# Ethernet_-_LAN8720A.net
KiCad netlist of a schematic drawn in Altium Designer
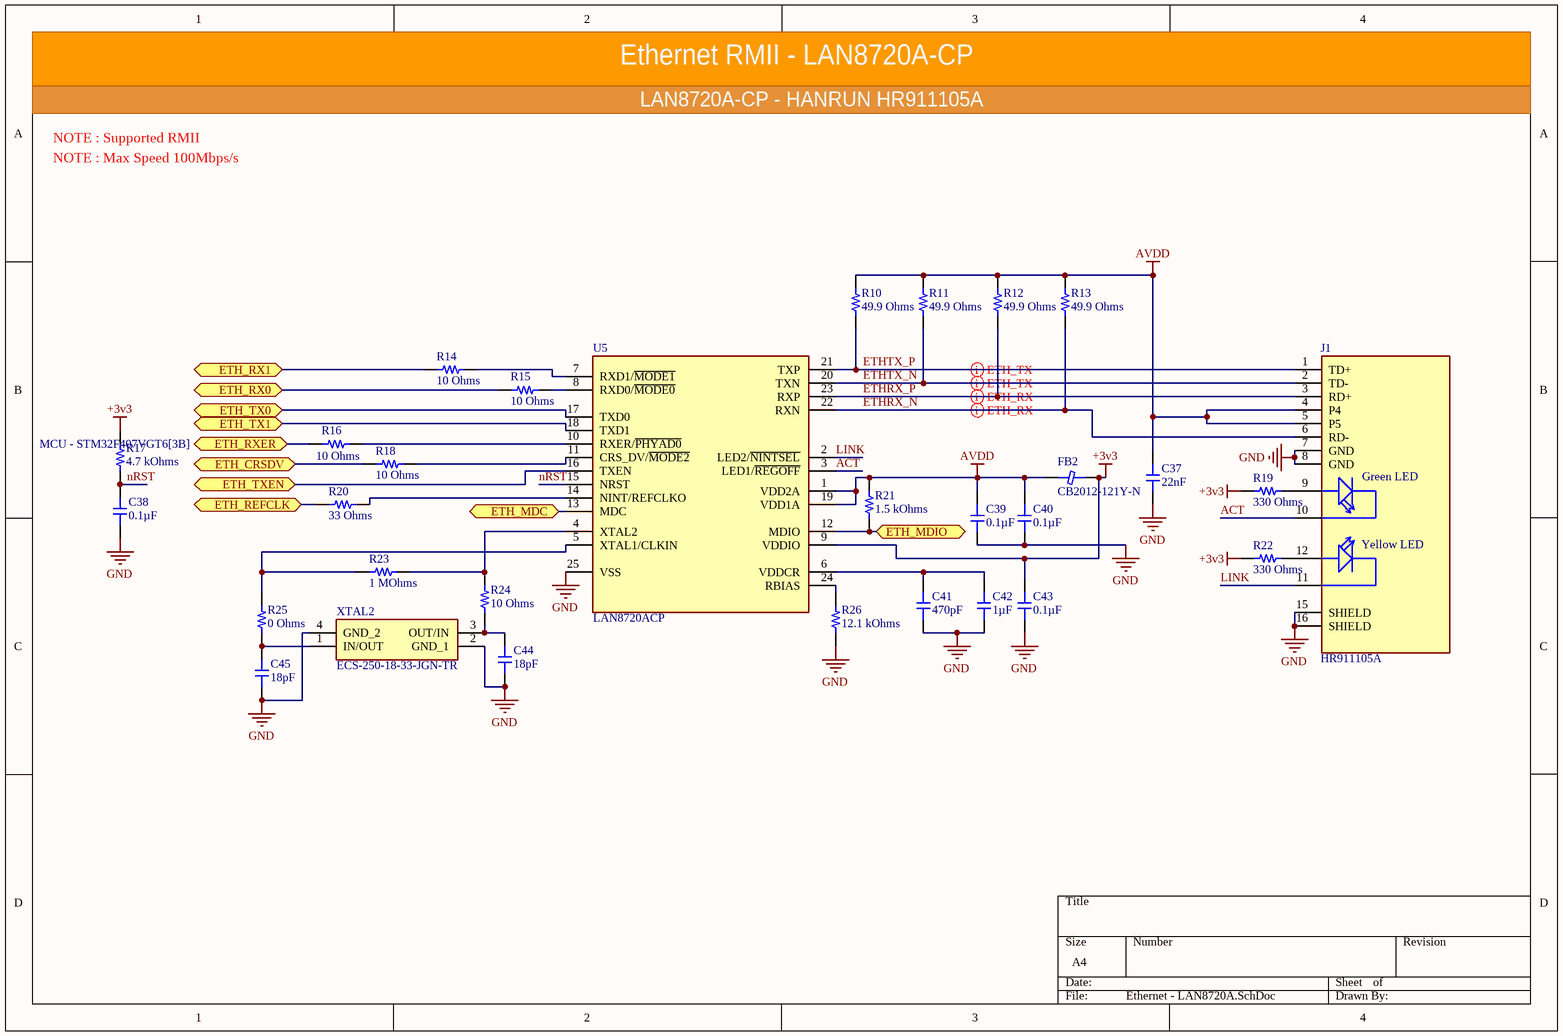
[diagram p0: Ethernet - LAN8720A.SchDoc]

(export (version "E")
  (design (tool "Eeschema 10.0.6"))
  (components
    (comp (ref "C37")
      (value "22nF")
      (footprint "0603_Footprint")
      (description "22nF 0603 Surface Capacitor")
      (libsource (lib "ELK_H7-V2 Library") (part "22nF 0603"))
    )
    (comp (ref "C38")
      (value "0.1µF")
      (footprint "0603_Footprint")
      (description "0.1uF 0603 Surface Capacitor")
      (libsource (lib "ELK_H7-V2 Library") (part "0.1uF 0603 Surface Capacitor_1_1_1_1_1_1"))
    )
    (comp (ref "C39")
      (value "0.1µF")
      (footprint "0603_Footprint")
      (description "0.1uF 0603 Surface Capacitor")
      (libsource (lib "ELK_H7-V2 Library") (part "0.1uF 0603 Surface Capacitor_1_1_1_1_1_1"))
    )
    (comp (ref "C40")
      (value "0.1µF")
      (footprint "0603_Footprint")
      (description "0.1uF 0603 Surface Capacitor")
      (libsource (lib "ELK_H7-V2 Library") (part "0.1uF 0603 Surface Capacitor_1_1_1_1_1_1"))
    )
    (comp (ref "C41")
      (value "470pF")
      (footprint "0603_Footprint")
      (description "470 pF 0603 Surface Capacitor")
      (libsource (lib "ELK_H7-V2 Library") (part "470 pF 0603 Surface Capacitor"))
    )
    (comp (ref "C42")
      (value "1µF")
      (footprint "0603_Footprint")
      (description "1uF 0603 Surface Capacitor")
      (libsource (lib "ELK_H7-V2 Library") (part "1uF 0603 Surface Capacitor"))
    )
    (comp (ref "C43")
      (value "0.1µF")
      (footprint "0603_Footprint")
      (description "0.1uF 0603 Surface Capacitor")
      (libsource (lib "ELK_H7-V2 Library") (part "0.1uF 0603 Surface Capacitor_1_1_1_1_1_1"))
    )
    (comp (ref "C44")
      (value "18pF")
      (footprint "0603_Footprint")
      (description "18pF 0603 Surface Capacitor")
      (libsource (lib "ELK_H7-V2 Library") (part "18pF 0603 Surface Capacitor"))
    )
    (comp (ref "C45")
      (value "18pF")
      (footprint "0603_Footprint")
      (description "18pF 0603 Surface Capacitor")
      (libsource (lib "ELK_H7-V2 Library") (part "18pF 0603 Surface Capacitor"))
    )
    (comp (ref "FB2")
      (value "CB2012-121Y-N")
      (footprint "Inductor-0603")
      (libsource (lib "ELK_H7-V2 Library") (part "CB2012-121Y-N"))
    )
    (comp (ref "J1")
      (value "HR911105A")
      (footprint "HANRUN_HR911105A")
      (description "DIP RJ45 Connector;")
      (fields (field (name "MF") "hanrun"))
      (libsource (lib "ELK_H7-V2 Library") (part "HR911105A"))
    )
    (comp (ref "R10")
      (value "49.9 Ohms")
      (footprint "0603_RES")
      (description "49.9 Ohms 0603")
      (libsource (lib "ELK_H7-V2 Library") (part "49.9 Ohms 0603"))
    )
    (comp (ref "R11")
      (value "49.9 Ohms")
      (footprint "0603_RES")
      (description "49.9 Ohms 0603")
      (libsource (lib "ELK_H7-V2 Library") (part "49.9 Ohms 0603"))
    )
    (comp (ref "R12")
      (value "49.9 Ohms")
      (footprint "0603_RES")
      (description "49.9 Ohms 0603")
      (libsource (lib "ELK_H7-V2 Library") (part "49.9 Ohms 0603"))
    )
    (comp (ref "R13")
      (value "49.9 Ohms")
      (footprint "0603_RES")
      (description "49.9 Ohms 0603")
      (libsource (lib "ELK_H7-V2 Library") (part "49.9 Ohms 0603"))
    )
    (comp (ref "R14")
      (value "10 Ohms")
      (footprint "0603_RES")
      (description "10 Ohms 0603")
      (libsource (lib "ELK_H7-V2 Library") (part "10 Ohm 0603"))
    )
    (comp (ref "R15")
      (value "10 Ohms")
      (footprint "0603_RES")
      (description "10 Ohms 0603")
      (libsource (lib "ELK_H7-V2 Library") (part "10 Ohm 0603"))
    )
    (comp (ref "R16")
      (value "10 Ohms")
      (footprint "0603_RES")
      (description "10 Ohms 0603")
      (libsource (lib "ELK_H7-V2 Library") (part "10 Ohm 0603"))
    )
    (comp (ref "R17")
      (value "4.7 kOhms")
      (footprint "0603_RES")
      (description "4.7 kOhms 0603")
      (libsource (lib "ELK_H7-V2 Library") (part "4.7 kOhms 0603"))
    )
    (comp (ref "R18")
      (value "10 Ohms")
      (footprint "0603_RES")
      (description "10 Ohms 0603")
      (libsource (lib "ELK_H7-V2 Library") (part "10 Ohm 0603"))
    )
    (comp (ref "R19")
      (value "330 Ohms")
      (footprint "0603_RES")
      (description "330 Ohm 0603")
      (libsource (lib "ELK_H7-V2 Library") (part "330 Ohm 0603"))
    )
    (comp (ref "R20")
      (value "33 Ohms")
      (footprint "0603_RES")
      (description "33 Ohm 0603")
      (libsource (lib "ELK_H7-V2 Library") (part "33 Ohm 0603"))
    )
    (comp (ref "R21")
      (value "1.5 kOhms")
      (footprint "0603_RES")
      (description "1.5 kOhms 0603")
      (libsource (lib "ELK_H7-V2 Library") (part "1.5 kOhms 0603"))
    )
    (comp (ref "R22")
      (value "330 Ohms")
      (footprint "0603_RES")
      (description "330 Ohm 0603")
      (libsource (lib "ELK_H7-V2 Library") (part "330 Ohm 0603"))
    )
    (comp (ref "R23")
      (value "1 MOhms")
      (footprint "0603_RES")
      (description "1 MOhms 0603")
      (libsource (lib "ELK_H7-V2 Library") (part "1 MOhms 0603"))
    )
    (comp (ref "R24")
      (value "10 Ohms")
      (footprint "0603_RES")
      (description "10 Ohms 0603")
      (libsource (lib "ELK_H7-V2 Library") (part "10 Ohm 0603"))
    )
    (comp (ref "R25")
      (value "0 Ohms")
      (footprint "0603_RES")
      (description "0 Ohm 0603")
      (libsource (lib "ELK_H7-V2 Library") (part "0 Ohm 0603"))
    )
    (comp (ref "R26")
      (value "12.1 kOhms")
      (footprint "0603_RES")
      (description "12.1 kOhms 0603")
      (libsource (lib "ELK_H7-V2 Library") (part "12.1 kOhms 0603"))
    )
    (comp (ref "U5")
      (value "LAN8720ACP")
      (footprint "QFN50P400X400X100-25N-D")
      (description "Ethernet Transreceiver")
      (libsource (lib "ELK_H7-V2 Library") (part "LAN8720ACP"))
    )
    (comp (ref "XTAL2")
      (value "ECS-250-18-33-JGN-TR")
      (footprint "ECS2501833JGNTR")
      (description "Crystal or Oscillator")
      (fields (field (name "MOUSER PART NUMBER") "520-250-18-33-JGNT"))
      (libsource (lib "ELK_H7-V2 Library") (part "ECS-250-18-33-JGN-TR"))
    )
  )
  (nets
    (net (code "1") (name "+3v3") (class "Default")
      (node (ref "C43") (pin "1") (pinfunction "1_1") (pintype "passive"))
      (node (ref "FB2") (pin "2") (pinfunction "2_2") (pintype "passive"))
      (node (ref "R17") (pin "2") (pinfunction "2_2") (pintype "passive"))
      (node (ref "R19") (pin "2") (pinfunction "2_2") (pintype "passive"))
      (node (ref "R22") (pin "2") (pinfunction "2_2") (pintype "passive"))
      (node (ref "U5") (pin "9") (pinfunction "VDDIO_9") (pintype "passive"))
    )
    (net (code "2") (name "/ACT") (class "Default")
      (node (ref "J1") (pin "10") (pinfunction "GC_10") (pintype "passive"))
      (node (ref "U5") (pin "3") (pinfunction "LED1/~{REGOFF}_3") (pintype "passive"))
    )
    (net (code "3") (name "/ETHRX_N") (class "Default")
      (node (ref "J1") (pin "6") (pinfunction "RD-_6") (pintype "passive"))
      (node (ref "R13") (pin "1") (pinfunction "1_1") (pintype "passive"))
      (node (ref "U5") (pin "22") (pinfunction "RXN_22") (pintype "passive"))
    )
    (net (code "4") (name "/ETHRX_P") (class "Default")
      (node (ref "J1") (pin "3") (pinfunction "RD+_3") (pintype "passive"))
      (node (ref "R12") (pin "1") (pinfunction "1_1") (pintype "passive"))
      (node (ref "U5") (pin "23") (pinfunction "RXP_23") (pintype "passive"))
    )
    (net (code "5") (name "/ETHTX_N") (class "Default")
      (node (ref "J1") (pin "2") (pinfunction "TD-_2") (pintype "passive"))
      (node (ref "R11") (pin "1") (pinfunction "1_1") (pintype "passive"))
      (node (ref "U5") (pin "20") (pinfunction "TXN_20") (pintype "passive"))
    )
    (net (code "6") (name "/ETHTX_P") (class "Default")
      (node (ref "J1") (pin "1") (pinfunction "TD+_1") (pintype "passive"))
      (node (ref "R10") (pin "1") (pinfunction "1_1") (pintype "passive"))
      (node (ref "U5") (pin "21") (pinfunction "TXP_21") (pintype "passive"))
    )
    (net (code "7") (name "/ETH_CRSDV") (class "Default")
      (node (ref "R18") (pin "1") (pinfunction "1_1") (pintype "passive"))
    )
    (net (code "8") (name "/ETH_MDC") (class "Default")
      (node (ref "U5") (pin "13") (pinfunction "MDC_13") (pintype "passive"))
    )
    (net (code "9") (name "/ETH_MDIO") (class "Default")
      (node (ref "R21") (pin "2") (pinfunction "2_2") (pintype "passive"))
      (node (ref "U5") (pin "12") (pinfunction "MDIO_12") (pintype "passive"))
    )
    (net (code "10") (name "/ETH_REFCLK") (class "Default")
      (node (ref "R20") (pin "1") (pinfunction "1_1") (pintype "passive"))
    )
    (net (code "11") (name "/ETH_RX0") (class "Default")
      (node (ref "R15") (pin "1") (pinfunction "1_1") (pintype "passive"))
    )
    (net (code "12") (name "/ETH_RX1") (class "Default")
      (node (ref "R14") (pin "1") (pinfunction "1_1") (pintype "passive"))
    )
    (net (code "13") (name "/ETH_RXER") (class "Default")
      (node (ref "R16") (pin "1") (pinfunction "1_1") (pintype "passive"))
    )
    (net (code "14") (name "/ETH_TX0") (class "Default")
      (node (ref "U5") (pin "17") (pinfunction "TXD0_17") (pintype "passive"))
    )
    (net (code "15") (name "/ETH_TX1") (class "Default")
      (node (ref "U5") (pin "18") (pinfunction "TXD1_18") (pintype "passive"))
    )
    (net (code "16") (name "/ETH_TXEN") (class "Default")
      (node (ref "U5") (pin "16") (pinfunction "TXEN_16") (pintype "passive"))
    )
    (net (code "17") (name "/LINK") (class "Default")
      (node (ref "J1") (pin "11") (pinfunction "YC_11") (pintype "passive"))
      (node (ref "U5") (pin "2") (pinfunction "LED2/~{NINTSEL}_2") (pintype "passive"))
    )
    (net (code "18") (name "/nRST") (class "Default")
      (node (ref "C38") (pin "1") (pinfunction "1_1") (pintype "passive"))
      (node (ref "R17") (pin "1") (pinfunction "1_1") (pintype "passive"))
      (node (ref "U5") (pin "15") (pinfunction "NRST_15") (pintype "passive"))
    )
    (net (code "19") (name "AVDD") (class "Default")
      (node (ref "C37") (pin "1") (pinfunction "1_1") (pintype "passive"))
      (node (ref "C39") (pin "1") (pinfunction "1_1") (pintype "passive"))
      (node (ref "C40") (pin "1") (pinfunction "1_1") (pintype "passive"))
      (node (ref "FB2") (pin "1") (pinfunction "1_1") (pintype "passive"))
      (node (ref "J1") (pin "4") (pinfunction "P4_4") (pintype "passive"))
      (node (ref "J1") (pin "5") (pinfunction "P5_5") (pintype "passive"))
      (node (ref "R10") (pin "2") (pinfunction "2_2") (pintype "passive"))
      (node (ref "R11") (pin "2") (pinfunction "2_2") (pintype "passive"))
      (node (ref "R12") (pin "2") (pinfunction "2_2") (pintype "passive"))
      (node (ref "R13") (pin "2") (pinfunction "2_2") (pintype "passive"))
      (node (ref "R21") (pin "1") (pinfunction "1_1") (pintype "passive"))
      (node (ref "U5") (pin "1") (pinfunction "VDD2A_1") (pintype "passive"))
      (node (ref "U5") (pin "19") (pinfunction "VDD1A_19") (pintype "passive"))
    )
    (net (code "20") (name "GND") (class "Default")
      (node (ref "C37") (pin "2") (pinfunction "2_2") (pintype "passive"))
      (node (ref "C38") (pin "2") (pinfunction "2_2") (pintype "passive"))
      (node (ref "C39") (pin "2") (pinfunction "2_2") (pintype "passive"))
      (node (ref "C40") (pin "2") (pinfunction "2_2") (pintype "passive"))
      (node (ref "C41") (pin "2") (pinfunction "2_2") (pintype "passive"))
      (node (ref "C42") (pin "1") (pinfunction "1_1") (pintype "passive"))
      (node (ref "C43") (pin "2") (pinfunction "2_2") (pintype "passive"))
      (node (ref "C44") (pin "2") (pinfunction "2_2") (pintype "passive"))
      (node (ref "C45") (pin "2") (pinfunction "2_2") (pintype "passive"))
      (node (ref "J1") (pin "15") (pinfunction "SHIELD_15") (pintype "passive"))
      (node (ref "J1") (pin "16") (pinfunction "SHIELD_16") (pintype "passive"))
      (node (ref "J1") (pin "7") (pinfunction "GND_7") (pintype "power_in"))
      (node (ref "J1") (pin "8") (pinfunction "GND_8") (pintype "power_in"))
      (node (ref "R26") (pin "1") (pinfunction "1_1") (pintype "passive"))
      (node (ref "U5") (pin "25") (pinfunction "VSS_25") (pintype "passive"))
      (node (ref "XTAL2") (pin "2") (pinfunction "GND_1_2") (pintype "passive"))
      (node (ref "XTAL2") (pin "4") (pinfunction "GND_2_4") (pintype "passive"))
    )
    (net (code "21") (name "Net-(J1-GA)") (class "Default")
      (node (ref "J1") (pin "9") (pinfunction "GA_9") (pintype "passive"))
      (node (ref "R19") (pin "1") (pinfunction "1_1") (pintype "passive"))
    )
    (net (code "22") (name "Net-(J1-YA)") (class "Default")
      (node (ref "J1") (pin "12") (pinfunction "YA_12") (pintype "passive"))
      (node (ref "R22") (pin "1") (pinfunction "1_1") (pintype "passive"))
    )
    (net (code "23") (name "Net-(U5-CRS_DV{slash}~{MODE2})") (class "Default")
      (node (ref "R18") (pin "2") (pinfunction "2_2") (pintype "passive"))
      (node (ref "U5") (pin "11") (pinfunction "CRS_DV/~{MODE2}_11") (pintype "passive"))
    )
    (net (code "24") (name "Net-(U5-NINT{slash}REFCLKO)") (class "Default")
      (node (ref "R20") (pin "2") (pinfunction "2_2") (pintype "passive"))
      (node (ref "U5") (pin "14") (pinfunction "NINT/REFCLKO_14") (pintype "passive"))
    )
    (net (code "25") (name "Net-(U5-RBIAS)") (class "Default")
      (node (ref "R26") (pin "2") (pinfunction "2_2") (pintype "passive"))
      (node (ref "U5") (pin "24") (pinfunction "RBIAS_24") (pintype "passive"))
    )
    (net (code "26") (name "Net-(U5-RXD0{slash}~{MODE0})") (class "Default")
      (node (ref "R15") (pin "2") (pinfunction "2_2") (pintype "passive"))
      (node (ref "U5") (pin "8") (pinfunction "RXD0/~{MODE0}_8") (pintype "passive"))
    )
    (net (code "27") (name "Net-(U5-RXD1{slash}~{MODE1})") (class "Default")
      (node (ref "R14") (pin "2") (pinfunction "2_2") (pintype "passive"))
      (node (ref "U5") (pin "7") (pinfunction "RXD1/~{MODE1}_7") (pintype "passive"))
    )
    (net (code "28") (name "Net-(U5-RXER{slash}~{PHYAD0})") (class "Default")
      (node (ref "R16") (pin "2") (pinfunction "2_2") (pintype "passive"))
      (node (ref "U5") (pin "10") (pinfunction "RXER/~{PHYAD0}_10") (pintype "passive"))
    )
    (net (code "29") (name "Net-(U5-VDDCR)") (class "Default")
      (node (ref "C41") (pin "1") (pinfunction "1_1") (pintype "passive"))
      (node (ref "C42") (pin "2") (pinfunction "2_2") (pintype "passive"))
      (node (ref "U5") (pin "6") (pinfunction "VDDCR_6") (pintype "passive"))
    )
    (net (code "30") (name "Net-(U5-XTAL1{slash}CLKIN)") (class "Default")
      (node (ref "R23") (pin "1") (pinfunction "1_1") (pintype "passive"))
      (node (ref "R25") (pin "2") (pinfunction "2_2") (pintype "passive"))
      (node (ref "U5") (pin "5") (pinfunction "XTAL1/CLKIN_5") (pintype "passive"))
    )
    (net (code "31") (name "Net-(U5-XTAL2)") (class "Default")
      (node (ref "R23") (pin "2") (pinfunction "2_2") (pintype "passive"))
      (node (ref "R24") (pin "1") (pinfunction "1_1") (pintype "passive"))
      (node (ref "U5") (pin "4") (pinfunction "XTAL2_4") (pintype "passive"))
    )
    (net (code "32") (name "Net-(XTAL2-IN{slash}OUT)") (class "Default")
      (node (ref "C45") (pin "1") (pinfunction "1_1") (pintype "passive"))
      (node (ref "R25") (pin "1") (pinfunction "1_1") (pintype "passive"))
      (node (ref "XTAL2") (pin "1") (pinfunction "IN/OUT_1") (pintype "passive"))
    )
    (net (code "33") (name "Net-(XTAL2-OUT{slash}IN)") (class "Default")
      (node (ref "C44") (pin "1") (pinfunction "1_1") (pintype "passive"))
      (node (ref "R24") (pin "2") (pinfunction "2_2") (pintype "passive"))
      (node (ref "XTAL2") (pin "3") (pinfunction "OUT/IN_3") (pintype "passive"))
    )
  )
)
